# nanobeam_soil_sensor.net
KiCad netlist of a schematic drawn in EAGLE
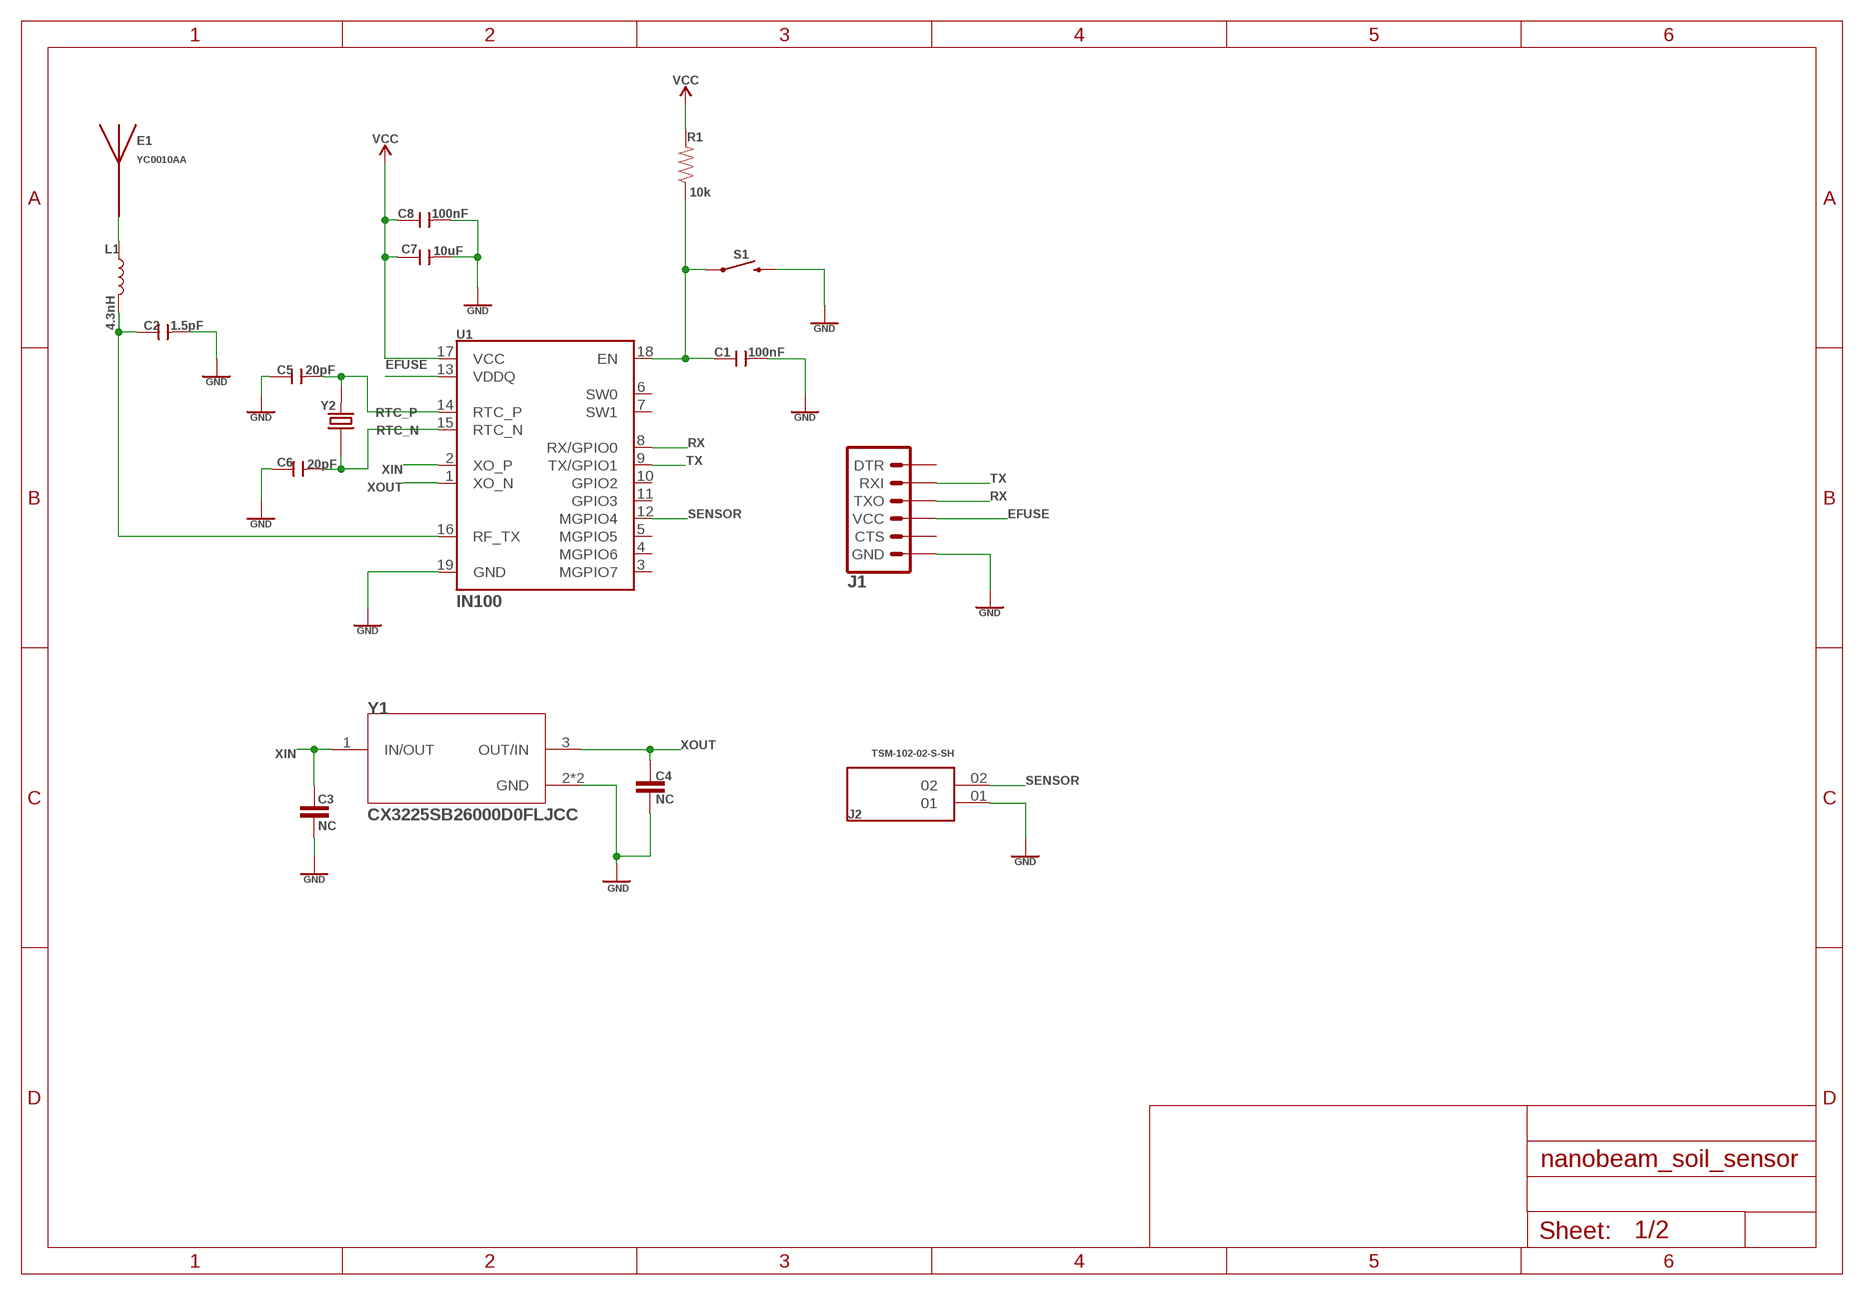
[diagram p0: schematic, sheet 1]
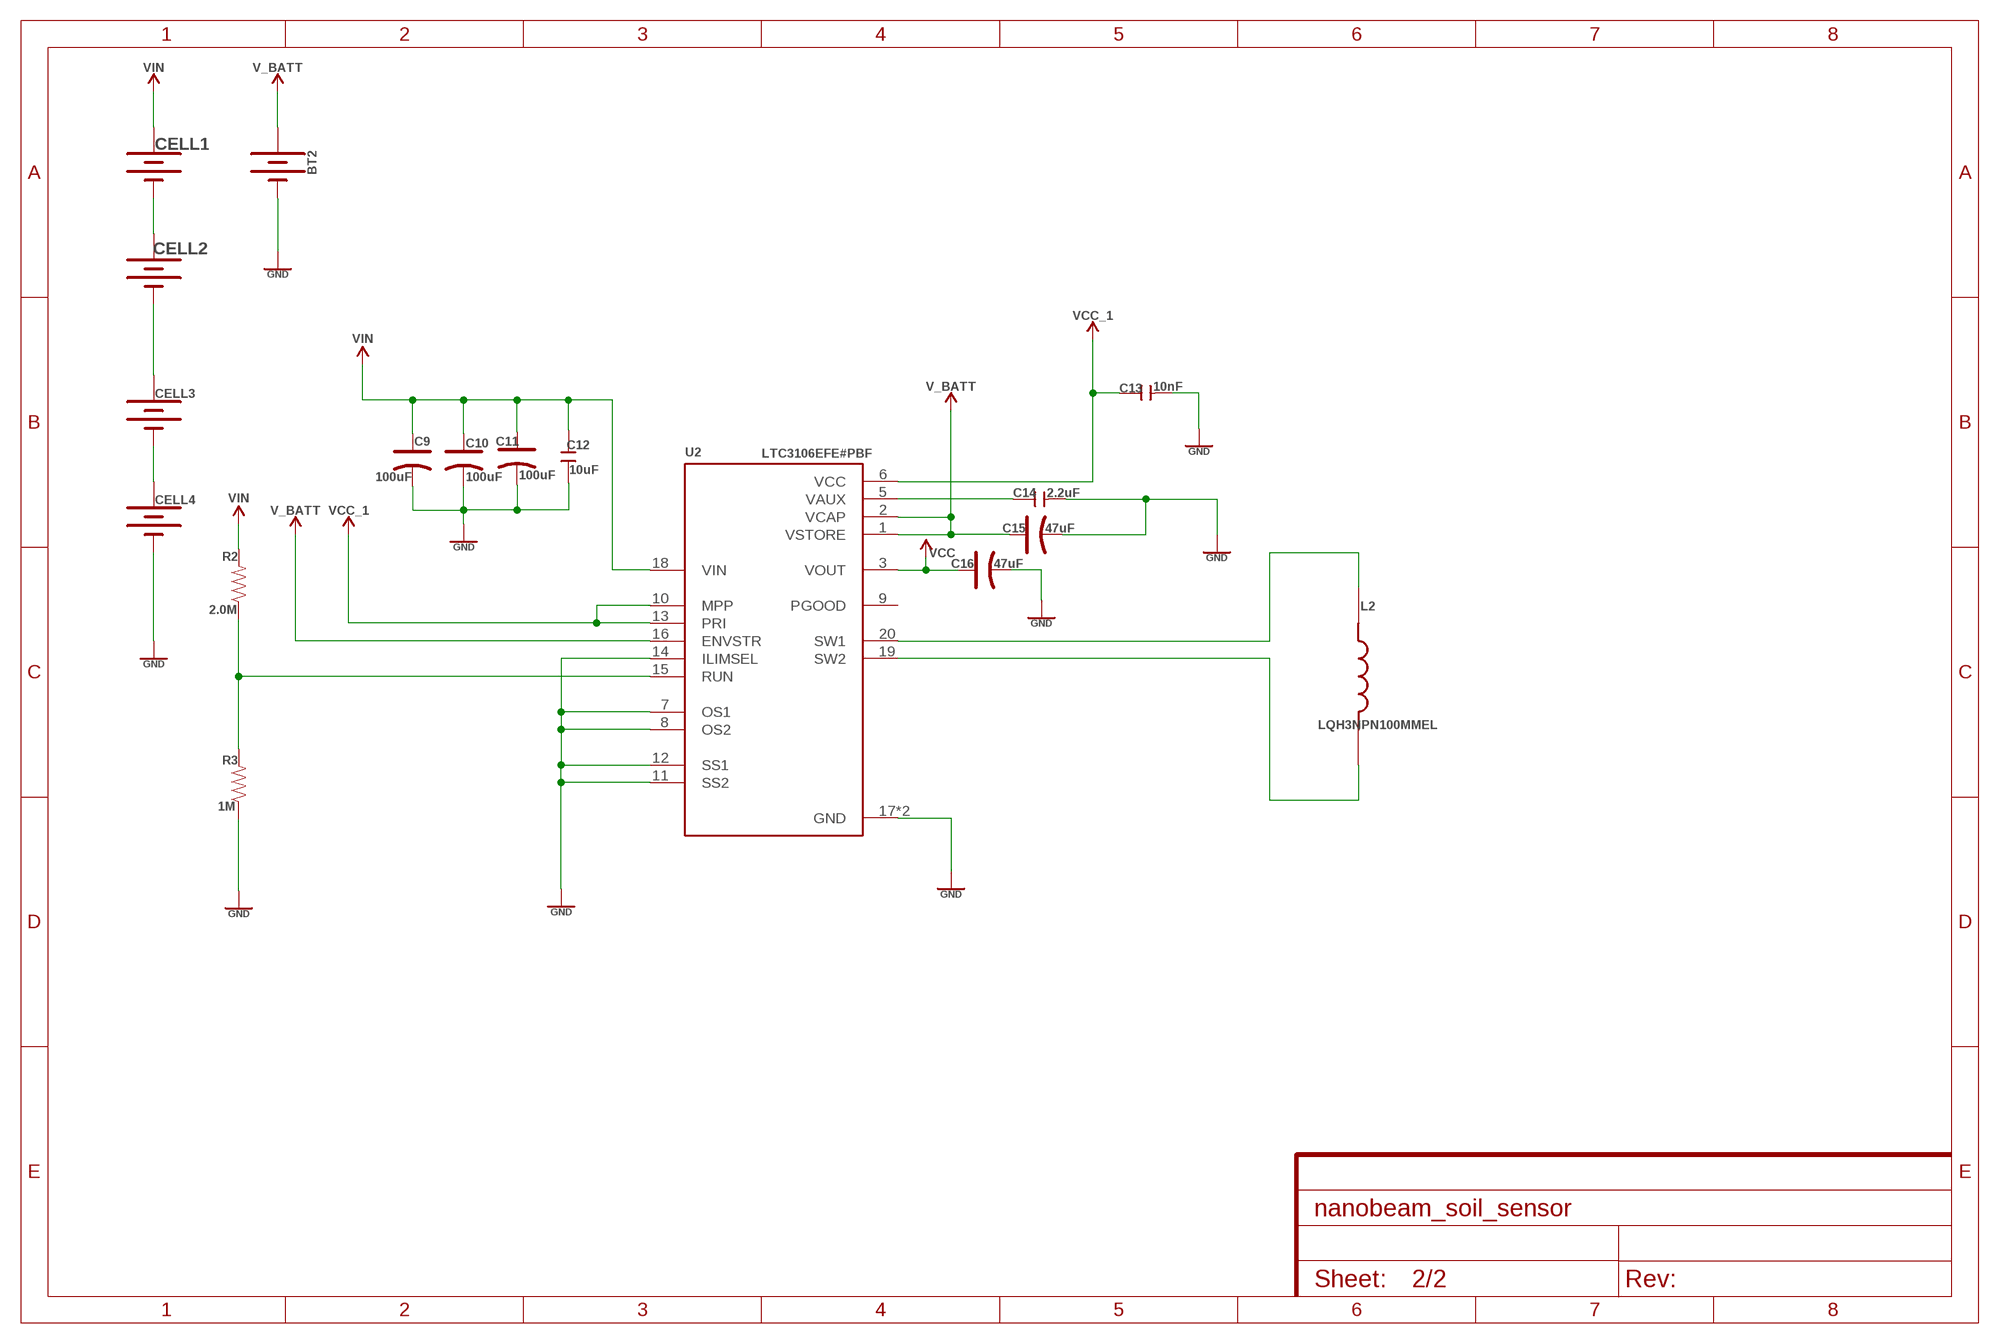
[diagram p1: schematic, sheet 2]

(export (version "E")
  (design (tool "Eeschema 10.0.6"))
  (components
    (comp (ref "C1")
      (value "100nF")
      (footprint "eagle-import:C0603")
      (fields (field (name "MPN") "CC0603KRX7R9BB104"))
      (libsource (lib "eagle-import") (part "CERAMIC-100NF-50V-10%-X7R(0603)"))
    )
    (comp (ref "C2")
      (value "1.5pF")
      (footprint "eagle-import:C0603")
      (fields (field (name "MPN") "CC0603JRNPO9BN100"))
      (libsource (lib "eagle-import") (part "CERAMIC-10PF-50V-5%-NPO(0603)"))
    )
    (comp (ref "C3")
      (value "NC")
      (footprint "eagle-import:0603")
      (libsource (lib "eagle-import") (part "12PF-0603-50V-5%"))
    )
    (comp (ref "C4")
      (value "NC")
      (footprint "eagle-import:0603")
      (libsource (lib "eagle-import") (part "12PF-0603-50V-5%"))
    )
    (comp (ref "C5")
      (value "20pF")
      (footprint "eagle-import:C0603")
      (fields (field (name "MPN") "CC0603JRNPO9BN220"))
      (libsource (lib "eagle-import") (part "CERAMIC-22PF-50V-5%-NPO(0603)"))
    )
    (comp (ref "C6")
      (value "20pF")
      (footprint "eagle-import:C0603")
      (fields (field (name "MPN") "CC0603JRNPO9BN220"))
      (libsource (lib "eagle-import") (part "CERAMIC-22PF-50V-5%-NPO(0603)"))
    )
    (comp (ref "C7")
      (value "10uF")
      (footprint "eagle-import:C0603")
      (fields (field (name "MPN") "CC0603KRX5R6BB106"))
      (libsource (lib "eagle-import") (part "CERAMIC-10UF-10V-10%-X5R(0603)"))
    )
    (comp (ref "C8")
      (value "100nF")
      (footprint "eagle-import:C0603")
      (fields (field (name "MPN") "CC0603KRX7R9BB104"))
      (libsource (lib "eagle-import") (part "CERAMIC-100NF-50V-10%-X7R(0603)"))
    )
    (comp (ref "E1")
      (value "YC0010AA")
      (footprint "eagle-import:XCVR_YC0010AA")
      (fields (field (name "MF") "Quectel"))
      (libsource (lib "eagle-import") (part "YC0010AA"))
    )
    (comp (ref "J1")
      (value "6_PIN_SERIAL_TARGETSMD")
      (footprint "eagle-import:1X06-SMD_RA_MALE")
      (libsource (lib "eagle-import") (part "6_PIN_SERIAL_TARGETSMD"))
    )
    (comp (ref "J2")
      (value "TSM-102-02-S-SH")
      (footprint "eagle-import:SAMTEC_TSM-102-02-S-SH")
      (fields (field (name "MF") "Samtec"))
      (libsource (lib "eagle-import") (part "TSM-102-02-S-SH"))
    )
    (comp (ref "L1")
      (value "4.3nH")
      (footprint "eagle-import:0603")
      (libsource (lib "eagle-import") (part "INDUCTOR-0603-33NH"))
    )
    (comp (ref "R1")
      (value "10k")
      (footprint "eagle-import:0603")
      (libsource (lib "eagle-import") (part "10KOHM-0603-1/10W-1%"))
    )
    (comp (ref "S1")
      (value "MOMENTARY-SWITCH-SPST-SMD-4.6X2.8MM")
      (footprint "eagle-import:TACTILE_SWITCH_SMD_4.6X2.8MM")
      (libsource (lib "eagle-import") (part "MOMENTARY-SWITCH-SPST-SMD-4.6X2.8MM"))
    )
    (comp (ref "U1")
      (value "IN100")
      (footprint "eagle-import:IN100")
      (libsource (lib "eagle-import") (part "IN100"))
    )
    (comp (ref "Y1")
      (value "CX3225SB26000D0FLJCC")
      (footprint "eagle-import:XTAL_ECS-480-8-33B-CWY-TR3")
      (fields
        (field (name "MF") "ECS Inc.")
        (field (name "MP") "ECS-480-8-33B-CWY-TR3")
        (field (name "MF_1") "Kyocera")
        (field (name "MP_1") "CX3225SB26000D0FLJCC")
      )
      (libsource (lib "eagle-import") (part "ECS-480-8-33B-CWY-TR3"))
    )
    (comp (ref "Y2")
      (value "ECS-.327-12.5-16-TR")
      (footprint "eagle-import:XTAL_ECS-.327-12.5-16-TR")
      (fields (field (name "MF") "ECS Inc."))
      (libsource (lib "eagle-import") (part "ECS-.327-12.5-16-TR"))
    )
    (comp (ref "BT2")
      (value "BATTERY-12MM_SMD")
      (footprint "eagle-import:BATTCON_12MM")
      (libsource (lib "eagle-import") (part "BATTERY-12MM_SMD"))
    )
    (comp (ref "C9")
      (value "100uF")
      (footprint "eagle-import:AVX-A")
      (fields (field (name "MPN") "TAJA476*006#NJ"))
      (libsource (lib "eagle-import") (part "TANTALUM-SMD-47UF-6.3V(AVX-A)"))
    )
    (comp (ref "C10")
      (value "100uF")
      (footprint "eagle-import:AVX-A")
      (fields (field (name "MPN") "TAJA476*006#NJ"))
      (libsource (lib "eagle-import") (part "TANTALUM-SMD-47UF-6.3V(AVX-A)"))
    )
    (comp (ref "C11")
      (value "100uF")
      (footprint "eagle-import:AVX-A")
      (fields (field (name "MPN") "TAJA476*006#NJ"))
      (libsource (lib "eagle-import") (part "TANTALUM-SMD-47UF-6.3V(AVX-A)"))
    )
    (comp (ref "C12")
      (value "10uF")
      (footprint "eagle-import:C0603")
      (fields (field (name "MPN") "CC0603MRX5R5BB106"))
      (libsource (lib "eagle-import") (part "CERAMIC-10UF-6.3V-20%-X5R(0603)"))
    )
    (comp (ref "C13")
      (value "10nF")
      (footprint "eagle-import:C0603")
      (fields (field (name "MPN") "CC0603KRX7R9BB103"))
      (libsource (lib "eagle-import") (part "CERAMIC-10NF-50V-10%-X7R(0603)"))
    )
    (comp (ref "C14")
      (value "2.2uF")
      (footprint "eagle-import:C0603")
      (fields (field (name "MPN") "CC0603KRX7R6BB225"))
      (libsource (lib "eagle-import") (part "CERAMIC-2.2UF-10V-10%-X7R(0603)"))
    )
    (comp (ref "C15")
      (value "47uF")
      (footprint "eagle-import:AVX-A")
      (fields (field (name "MPN") "TAJA476*006#NJ"))
      (libsource (lib "eagle-import") (part "TANTALUM-SMD-47UF-6.3V(AVX-A)"))
    )
    (comp (ref "C16")
      (value "47uF")
      (footprint "eagle-import:AVX-A")
      (fields (field (name "MPN") "TAJA476*006#NJ"))
      (libsource (lib "eagle-import") (part "TANTALUM-SMD-47UF-6.3V(AVX-A)"))
    )
    (comp (ref "CELL1")
      (value "KXOB25")
      (footprint "eagle-import:KXOB25")
      (libsource (lib "eagle-import") (part "KXOB25"))
    )
    (comp (ref "CELL2")
      (value "KXOB25")
      (footprint "eagle-import:KXOB25")
      (libsource (lib "eagle-import") (part "KXOB25"))
    )
    (comp (ref "CELL3")
      (value "KXOB25")
      (footprint "eagle-import:KXOB25")
      (libsource (lib "eagle-import") (part "KXOB25"))
    )
    (comp (ref "CELL4")
      (value "KXOB25")
      (footprint "eagle-import:KXOB25")
      (libsource (lib "eagle-import") (part "KXOB25"))
    )
    (comp (ref "L2")
      (value "LQH3NPN100MMEL")
      (footprint "eagle-import:IND_LQH3NPN100MMEL")
      (fields (field (name "DIGI-KEY_PART_NUMBER") "490-15945-1-ND") (field (name "MF") "Murata"))
      (libsource (lib "eagle-import") (part "LQH3NPN100MMEL"))
    )
    (comp (ref "R2")
      (value "2.0M")
      (footprint "eagle-import:0603")
      (libsource (lib "eagle-import") (part "2MOHMS-0603-1/10W-1%"))
    )
    (comp (ref "R3")
      (value "1M")
      (footprint "eagle-import:0603")
      (libsource (lib "eagle-import") (part "1MOHM-0603-1/4W-5%"))
    )
    (comp (ref "U2")
      (value "LTC3106EFE#PBF")
      (footprint "eagle-import:SOP65P640X120-21N")
      (fields (field (name "MF") "Analog Devices"))
      (libsource (lib "eagle-import") (part "LTC3106EFE#PBF"))
    )
  )
  (nets
    (net (code "1") (name "EFUSE") (class "Default")
      (node (ref "J1") (pin "4") (pinfunction "VCC_4") (pintype "passive"))
      (node (ref "U1") (pin "13") (pinfunction "VDDQ_13") (pintype "power_in"))
    )
    (net (code "2") (name "GND") (class "Default")
      (node (ref "BT2") (pin "GND") (pinfunction "-_GND") (pintype "power_in"))
      (node (ref "C1") (pin "2") (pinfunction "2_2") (pintype "passive"))
      (node (ref "C10") (pin "-") (pinfunction "-_-") (pintype "passive"))
      (node (ref "C11") (pin "-") (pinfunction "-_-") (pintype "passive"))
      (node (ref "C12") (pin "1") (pinfunction "1_1") (pintype "passive"))
      (node (ref "C13") (pin "2") (pinfunction "2_2") (pintype "passive"))
      (node (ref "C14") (pin "2") (pinfunction "2_2") (pintype "passive"))
      (node (ref "C15") (pin "-") (pinfunction "-_-") (pintype "passive"))
      (node (ref "C16") (pin "-") (pinfunction "-_-") (pintype "passive"))
      (node (ref "C2") (pin "2") (pinfunction "2_2") (pintype "passive"))
      (node (ref "C3") (pin "2") (pinfunction "2_2") (pintype "passive"))
      (node (ref "C4") (pin "2") (pinfunction "2_2") (pintype "passive"))
      (node (ref "C5") (pin "1") (pinfunction "1_1") (pintype "passive"))
      (node (ref "C6") (pin "1") (pinfunction "1_1") (pintype "passive"))
      (node (ref "C7") (pin "2") (pinfunction "2_2") (pintype "passive"))
      (node (ref "C8") (pin "2") (pinfunction "2_2") (pintype "passive"))
      (node (ref "C9") (pin "-") (pinfunction "-_-") (pintype "passive"))
      (node (ref "CELL4") (pin "-") (pinfunction "-_-") (pintype "power_in"))
      (node (ref "J1") (pin "6") (pinfunction "GND_6") (pintype "passive"))
      (node (ref "J2") (pin "01") (pinfunction "01_01") (pintype "passive"))
      (node (ref "R3") (pin "1") (pinfunction "1_1") (pintype "passive"))
      (node (ref "S1") (pin "3") (pinfunction "2_3") (pintype "passive"))
      (node (ref "S1") (pin "4") (pinfunction "2_4") (pintype "passive"))
      (node (ref "U1") (pin "19") (pinfunction "GND_19") (pintype "power_in"))
      (node (ref "U2") (pin "11") (pinfunction "SS2_11") (pintype "input"))
      (node (ref "U2") (pin "12") (pinfunction "SS1_12") (pintype "input"))
      (node (ref "U2") (pin "14") (pinfunction "ILIMSEL_14") (pintype "input"))
      (node (ref "U2") (pin "17") (pinfunction "GND_17") (pintype "power_in"))
      (node (ref "U2") (pin "21") (pinfunction "GND_21") (pintype "power_in"))
      (node (ref "U2") (pin "7") (pinfunction "OS1_7") (pintype "input"))
      (node (ref "U2") (pin "8") (pinfunction "OS2_8") (pintype "input"))
      (node (ref "Y1") (pin "2") (pinfunction "GND_2") (pintype "power_in"))
      (node (ref "Y1") (pin "4") (pinfunction "GND_4") (pintype "power_in"))
    )
    (net (code "3") (name "Net-(CELL1-Pad-)") (class "Default")
      (node (ref "CELL1") (pin "-") (pinfunction "-_-") (pintype "power_in"))
      (node (ref "CELL2") (pin "+") (pinfunction "+_+") (pintype "power_in"))
    )
    (net (code "4") (name "Net-(CELL2-Pad-)") (class "Default")
      (node (ref "CELL2") (pin "-") (pinfunction "-_-") (pintype "power_in"))
      (node (ref "CELL3") (pin "+") (pinfunction "+_+") (pintype "power_in"))
    )
    (net (code "5") (name "Net-(CELL3-Pad-)") (class "Default")
      (node (ref "CELL3") (pin "-") (pinfunction "-_-") (pintype "power_in"))
      (node (ref "CELL4") (pin "+") (pinfunction "+_+") (pintype "power_in"))
    )
    (net (code "6") (name "Net-(E1-Pad1)") (class "Default")
      (node (ref "E1") (pin "1") (pinfunction "1_1") (pintype "input"))
      (node (ref "L1") (pin "1") (pinfunction "1_1") (pintype "passive"))
    )
    (net (code "7") (name "Net-(U1-EN)") (class "Default")
      (node (ref "C1") (pin "1") (pinfunction "1_1") (pintype "passive"))
      (node (ref "R1") (pin "1") (pinfunction "1_1") (pintype "passive"))
      (node (ref "S1") (pin "1") (pinfunction "1_1") (pintype "passive"))
      (node (ref "S1") (pin "2") (pinfunction "1_2") (pintype "passive"))
      (node (ref "U1") (pin "18") (pinfunction "EN_18") (pintype "input"))
    )
    (net (code "8") (name "Net-(U1-RF_TX)") (class "Default")
      (node (ref "C2") (pin "1") (pinfunction "1_1") (pintype "passive"))
      (node (ref "L1") (pin "2") (pinfunction "2_2") (pintype "passive"))
      (node (ref "U1") (pin "16") (pinfunction "RF_TX_16") (pintype "bidirectional"))
    )
    (net (code "9") (name "Net-(U2-RUN)") (class "Default")
      (node (ref "R2") (pin "1") (pinfunction "1_1") (pintype "passive"))
      (node (ref "R3") (pin "2") (pinfunction "2_2") (pintype "passive"))
      (node (ref "U2") (pin "15") (pinfunction "RUN_15") (pintype "input"))
    )
    (net (code "10") (name "Net-(U2-SW1)") (class "Default")
      (node (ref "L2") (pin "1") (pinfunction "1_1") (pintype "passive"))
      (node (ref "U2") (pin "20") (pinfunction "SW1_20") (pintype "passive"))
    )
    (net (code "11") (name "Net-(U2-SW2)") (class "Default")
      (node (ref "L2") (pin "2") (pinfunction "2_2") (pintype "passive"))
      (node (ref "U2") (pin "19") (pinfunction "SW2_19") (pintype "passive"))
    )
    (net (code "12") (name "Net-(U2-VAUX)") (class "Default")
      (node (ref "C14") (pin "1") (pinfunction "1_1") (pintype "passive"))
      (node (ref "U2") (pin "5") (pinfunction "VAUX_5") (pintype "power_in"))
    )
    (net (code "13") (name "RTC_N") (class "Default")
      (node (ref "C6") (pin "2") (pinfunction "2_2") (pintype "passive"))
      (node (ref "U1") (pin "15") (pinfunction "RTC_N_15") (pintype "bidirectional"))
      (node (ref "Y2") (pin "1") (pinfunction "1_1") (pintype "passive"))
    )
    (net (code "14") (name "RTC_P") (class "Default")
      (node (ref "C5") (pin "2") (pinfunction "2_2") (pintype "passive"))
      (node (ref "U1") (pin "14") (pinfunction "RTC_P_14") (pintype "bidirectional"))
      (node (ref "Y2") (pin "2") (pinfunction "2_2") (pintype "passive"))
    )
    (net (code "15") (name "RX") (class "Default")
      (node (ref "J1") (pin "3") (pinfunction "TXO_3") (pintype "passive"))
      (node (ref "U1") (pin "8") (pinfunction "RX/GPIO0_8") (pintype "bidirectional"))
    )
    (net (code "16") (name "SENSOR") (class "Default")
      (node (ref "J2") (pin "02") (pinfunction "02_02") (pintype "passive"))
      (node (ref "U1") (pin "12") (pinfunction "MGPIO4_12") (pintype "bidirectional"))
    )
    (net (code "17") (name "TX") (class "Default")
      (node (ref "J1") (pin "2") (pinfunction "RXI_2") (pintype "passive"))
      (node (ref "U1") (pin "9") (pinfunction "TX/GPIO1_9") (pintype "bidirectional"))
    )
    (net (code "18") (name "VCC") (class "Default")
      (node (ref "C16") (pin "+") (pinfunction "+_+") (pintype "passive"))
      (node (ref "C7") (pin "1") (pinfunction "1_1") (pintype "passive"))
      (node (ref "C8") (pin "1") (pinfunction "1_1") (pintype "passive"))
      (node (ref "R1") (pin "2") (pinfunction "2_2") (pintype "passive"))
      (node (ref "U1") (pin "17") (pinfunction "VCC_17") (pintype "power_in"))
      (node (ref "U2") (pin "3") (pinfunction "VOUT_3") (pintype "output"))
    )
    (net (code "19") (name "VCC_1") (class "Default")
      (node (ref "C13") (pin "1") (pinfunction "1_1") (pintype "passive"))
      (node (ref "U2") (pin "10") (pinfunction "MPP_10") (pintype "input"))
      (node (ref "U2") (pin "13") (pinfunction "PRI_13") (pintype "input"))
      (node (ref "U2") (pin "6") (pinfunction "VCC_6") (pintype "power_in"))
    )
    (net (code "20") (name "VIN") (class "Default")
      (node (ref "C10") (pin "+") (pinfunction "+_+") (pintype "passive"))
      (node (ref "C11") (pin "+") (pinfunction "+_+") (pintype "passive"))
      (node (ref "C12") (pin "2") (pinfunction "2_2") (pintype "passive"))
      (node (ref "C9") (pin "+") (pinfunction "+_+") (pintype "passive"))
      (node (ref "CELL1") (pin "+") (pinfunction "+_+") (pintype "power_in"))
      (node (ref "R2") (pin "2") (pinfunction "2_2") (pintype "passive"))
      (node (ref "U2") (pin "18") (pinfunction "VIN_18") (pintype "input"))
    )
    (net (code "21") (name "V_BATT") (class "Default")
      (node (ref "BT2") (pin "PWR@1") (pinfunction "+_PWR@1") (pintype "power_in"))
      (node (ref "C15") (pin "+") (pinfunction "+_+") (pintype "passive"))
      (node (ref "U2") (pin "1") (pinfunction "VSTORE_1") (pintype "power_in"))
      (node (ref "U2") (pin "16") (pinfunction "ENVSTR_16") (pintype "input"))
      (node (ref "U2") (pin "2") (pinfunction "VCAP_2") (pintype "power_in"))
    )
    (net (code "22") (name "XIN") (class "Default")
      (node (ref "C3") (pin "1") (pinfunction "1_1") (pintype "passive"))
      (node (ref "U1") (pin "2") (pinfunction "XO_P_2") (pintype "bidirectional"))
      (node (ref "Y1") (pin "1") (pinfunction "IN/OUT_1") (pintype "bidirectional"))
    )
    (net (code "23") (name "XOUT") (class "Default")
      (node (ref "C4") (pin "1") (pinfunction "1_1") (pintype "passive"))
      (node (ref "U1") (pin "1") (pinfunction "XO_N_1") (pintype "bidirectional"))
      (node (ref "Y1") (pin "3") (pinfunction "OUT/IN_3") (pintype "bidirectional"))
    )
    (net (code "24") (name "unconnected-(J1-CTS-Pad5)") (class "Default")
      (node (ref "J1") (pin "5") (pinfunction "CTS_5") (pintype "passive"))
    )
    (net (code "25") (name "unconnected-(J1-DTR-Pad1)") (class "Default")
      (node (ref "J1") (pin "1") (pinfunction "DTR_1") (pintype "passive"))
    )
    (net (code "26") (name "unconnected-(U1-GPIO2-Pad10)") (class "Default")
      (node (ref "U1") (pin "10") (pinfunction "GPIO2_10") (pintype "bidirectional"))
    )
    (net (code "27") (name "unconnected-(U1-GPIO3-Pad11)") (class "Default")
      (node (ref "U1") (pin "11") (pinfunction "GPIO3_11") (pintype "bidirectional"))
    )
    (net (code "28") (name "unconnected-(U1-MGPIO5-Pad5)") (class "Default")
      (node (ref "U1") (pin "5") (pinfunction "MGPIO5_5") (pintype "bidirectional"))
    )
    (net (code "29") (name "unconnected-(U1-MGPIO6-Pad4)") (class "Default")
      (node (ref "U1") (pin "4") (pinfunction "MGPIO6_4") (pintype "bidirectional"))
    )
    (net (code "30") (name "unconnected-(U1-MGPIO7-Pad3)") (class "Default")
      (node (ref "U1") (pin "3") (pinfunction "MGPIO7_3") (pintype "bidirectional"))
    )
    (net (code "31") (name "unconnected-(U1-SW0-Pad6)") (class "Default")
      (node (ref "U1") (pin "6") (pinfunction "SW0_6") (pintype "output"))
    )
    (net (code "32") (name "unconnected-(U1-SW1-Pad7)") (class "Default")
      (node (ref "U1") (pin "7") (pinfunction "SW1_7") (pintype "output"))
    )
    (net (code "33") (name "unconnected-(U2-PGOOD-Pad9)") (class "Default")
      (node (ref "U2") (pin "9") (pinfunction "PGOOD_9") (pintype "output"))
    )
  )
)
